# EX_IO.net
KiCad netlist of a schematic drawn in Altium Designer
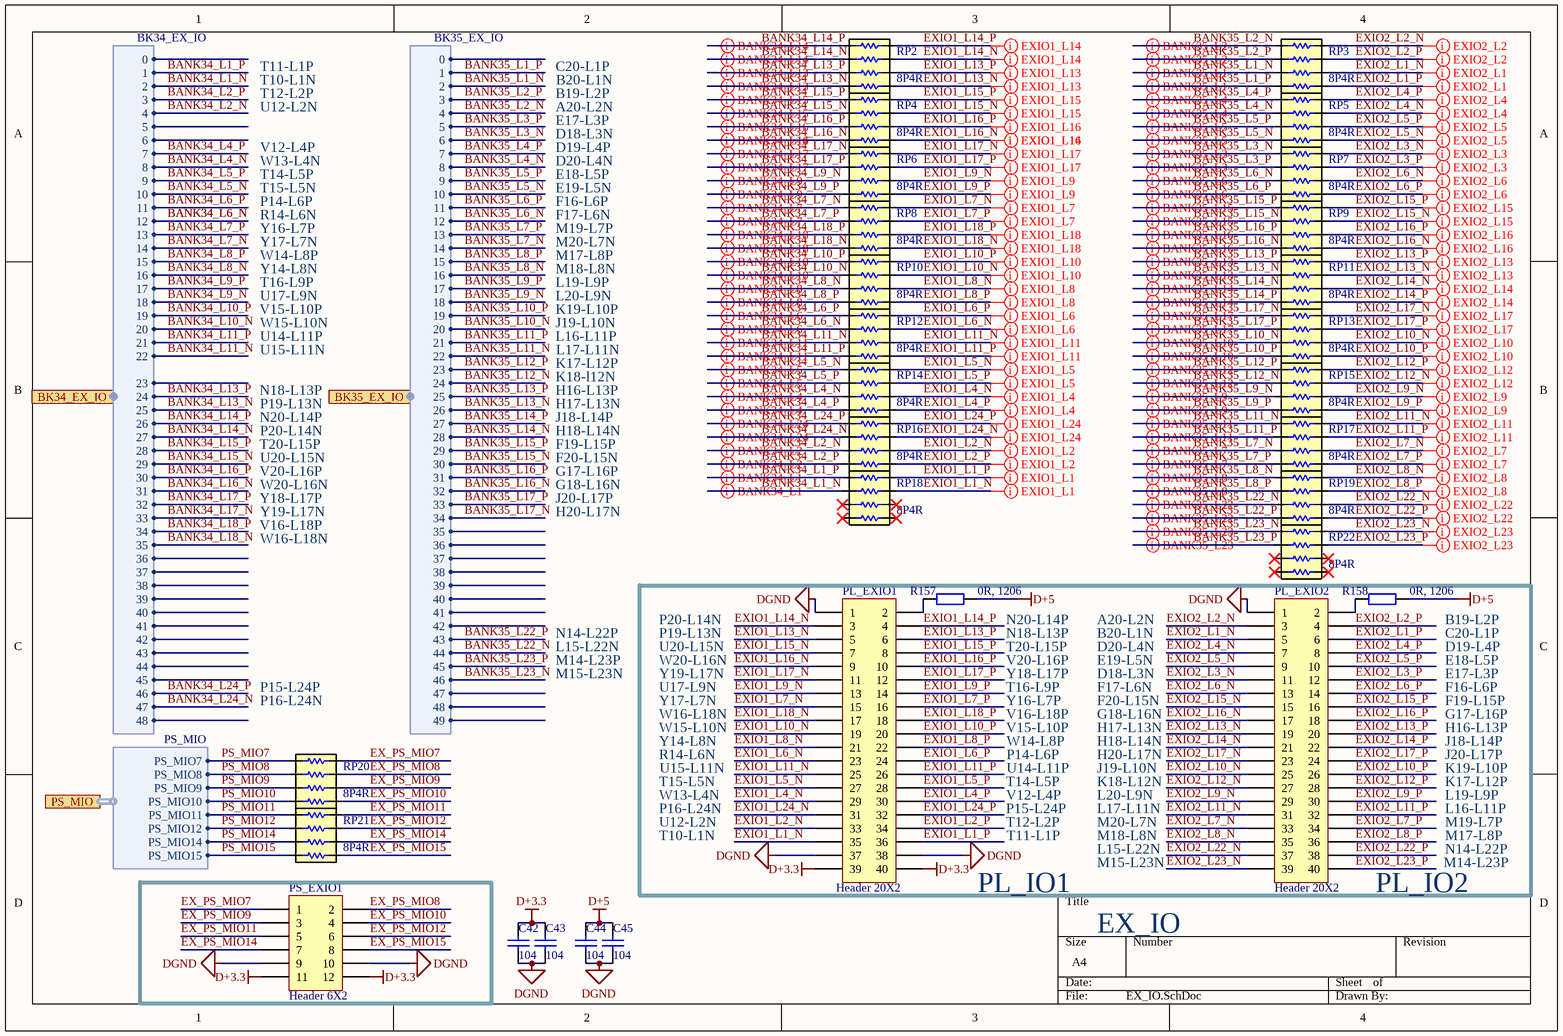
[diagram p0: EX_IO.SchDoc]

(export (version "E")
  (design (tool "Eeschema 10.0.6"))
  (components
    (comp (ref "C42")
      (value "104")
      (footprint "C 0402_LL")
      (description "Capacitor")
      (fields (field (name "PUBLISHER") "Altium Limited"))
      (libsource (lib "Miscellaneous Devices") (part "Cap"))
    )
    (comp (ref "C43")
      (value "104")
      (footprint "C 0402_LL")
      (description "Capacitor")
      (fields (field (name "PUBLISHER") "Altium Limited"))
      (libsource (lib "Miscellaneous Devices") (part "Cap"))
    )
    (comp (ref "C44")
      (value "104")
      (footprint "C 0402_LL")
      (description "Capacitor")
      (fields (field (name "PUBLISHER") "Altium Limited"))
      (libsource (lib "Miscellaneous Devices") (part "Cap"))
    )
    (comp (ref "C45")
      (value "104")
      (footprint "C 0402_LL")
      (description "Capacitor")
      (fields (field (name "PUBLISHER") "Altium Limited"))
      (libsource (lib "Miscellaneous Devices") (part "Cap"))
    )
    (comp (ref "PL_EXIO1")
      (value "Header 20X2")
      (footprint "HDR2.54-LI-2x20P")
      (description "Header, 20-Pin, Dual row")
      (fields (field (name "PUBLISHER") "Altium Limited"))
      (libsource (lib "Miscellaneous Connectors") (part "Header 20X2"))
    )
    (comp (ref "PL_EXIO2")
      (value "Header 20X2")
      (footprint "HDR2.54-LI-2x20P")
      (description "Header, 20-Pin, Dual row")
      (fields (field (name "PUBLISHER") "Altium Limited"))
      (libsource (lib "ZYNQ7010_add") (part "Header 20X2"))
    )
    (comp (ref "PS_EXIO1")
      (value "Header 6X2")
      (footprint "HDR2X6")
      (description "Header, 6-Pin, Dual row")
      (fields (field (name "PUBLISHER") "Altium Limited"))
      (libsource (lib "Miscellaneous Connectors") (part "Header 6X2"))
    )
    (comp (ref "R157")
      (value "0R, 1206")
      (footprint "R 1206_L")
      (description "Resistor")
      (fields (field (name "PUBLISHER") "Altium Limited"))
      (libsource (lib "Miscellaneous Devices") (part "Res2"))
    )
    (comp (ref "R158")
      (value "0R, 1206")
      (footprint "R 1206_L")
      (description "Resistor")
      (fields (field (name "PUBLISHER") "Altium Limited"))
      (libsource (lib "Miscellaneous Devices") (part "Res2"))
    )
    (comp (ref "RP2")
      (value "8P4R")
      (footprint "8P4R")
      (description "贴片排阻")
      (fields (field (name "MANUFACTURER") "NC"))
      (libsource (lib "ZYNQ7010_add") (part "8P4R"))
    )
    (comp (ref "RP3")
      (value "8P4R")
      (footprint "8P4R")
      (description "贴片排阻")
      (fields (field (name "MANUFACTURER") "NC"))
      (libsource (lib "ZYNQ7010_add") (part "8P4R"))
    )
    (comp (ref "RP4")
      (value "8P4R")
      (footprint "8P4R")
      (description "贴片排阻")
      (fields (field (name "MANUFACTURER") "NC"))
      (libsource (lib "ZYNQ7010_add") (part "8P4R"))
    )
    (comp (ref "RP5")
      (value "8P4R")
      (footprint "8P4R")
      (description "贴片排阻")
      (fields (field (name "MANUFACTURER") "NC"))
      (libsource (lib "ZYNQ7010_add") (part "8P4R"))
    )
    (comp (ref "RP6")
      (value "8P4R")
      (footprint "8P4R")
      (description "贴片排阻")
      (fields (field (name "MANUFACTURER") "NC"))
      (libsource (lib "ZYNQ7010_add") (part "8P4R"))
    )
    (comp (ref "RP7")
      (value "8P4R")
      (footprint "8P4R")
      (description "贴片排阻")
      (fields (field (name "MANUFACTURER") "NC"))
      (libsource (lib "ZYNQ7010_add") (part "8P4R"))
    )
    (comp (ref "RP8")
      (value "8P4R")
      (footprint "8P4R")
      (description "贴片排阻")
      (fields (field (name "MANUFACTURER") "NC"))
      (libsource (lib "ZYNQ7010_add") (part "8P4R"))
    )
    (comp (ref "RP9")
      (value "8P4R")
      (footprint "8P4R")
      (description "贴片排阻")
      (fields (field (name "MANUFACTURER") "NC"))
      (libsource (lib "ZYNQ7010_add") (part "8P4R"))
    )
    (comp (ref "RP10")
      (value "8P4R")
      (footprint "8P4R")
      (description "贴片排阻")
      (fields (field (name "MANUFACTURER") "NC"))
      (libsource (lib "ZYNQ7010_add") (part "8P4R"))
    )
    (comp (ref "RP11")
      (value "8P4R")
      (footprint "8P4R")
      (description "贴片排阻")
      (fields (field (name "MANUFACTURER") "NC"))
      (libsource (lib "ZYNQ7010_add") (part "8P4R"))
    )
    (comp (ref "RP12")
      (value "8P4R")
      (footprint "8P4R")
      (description "贴片排阻")
      (fields (field (name "MANUFACTURER") "NC"))
      (libsource (lib "ZYNQ7010_add") (part "8P4R"))
    )
    (comp (ref "RP13")
      (value "8P4R")
      (footprint "8P4R")
      (description "贴片排阻")
      (fields (field (name "MANUFACTURER") "NC"))
      (libsource (lib "ZYNQ7010_add") (part "8P4R"))
    )
    (comp (ref "RP14")
      (value "8P4R")
      (footprint "8P4R")
      (description "贴片排阻")
      (fields (field (name "MANUFACTURER") "NC"))
      (libsource (lib "ZYNQ7010_add") (part "8P4R"))
    )
    (comp (ref "RP15")
      (value "8P4R")
      (footprint "8P4R")
      (description "贴片排阻")
      (fields (field (name "MANUFACTURER") "NC"))
      (libsource (lib "ZYNQ7010_add") (part "8P4R"))
    )
    (comp (ref "RP16")
      (value "8P4R")
      (footprint "8P4R")
      (description "贴片排阻")
      (fields (field (name "MANUFACTURER") "NC"))
      (libsource (lib "ZYNQ7010_add") (part "8P4R"))
    )
    (comp (ref "RP17")
      (value "8P4R")
      (footprint "8P4R")
      (description "贴片排阻")
      (fields (field (name "MANUFACTURER") "NC"))
      (libsource (lib "ZYNQ7010_add") (part "8P4R"))
    )
    (comp (ref "RP18")
      (value "8P4R")
      (footprint "8P4R")
      (description "贴片排阻")
      (fields (field (name "MANUFACTURER") "NC"))
      (libsource (lib "ZYNQ7010_add") (part "8P4R"))
    )
    (comp (ref "RP19")
      (value "8P4R")
      (footprint "8P4R")
      (description "贴片排阻")
      (fields (field (name "MANUFACTURER") "NC"))
      (libsource (lib "ZYNQ7010_add") (part "8P4R"))
    )
    (comp (ref "RP20")
      (value "8P4R")
      (footprint "8P4R")
      (description "贴片排阻")
      (fields (field (name "MANUFACTURER") "NC"))
      (libsource (lib "ZYNQ7010_add") (part "8P4R"))
    )
    (comp (ref "RP21")
      (value "8P4R")
      (footprint "8P4R")
      (description "贴片排阻")
      (fields (field (name "MANUFACTURER") "NC"))
      (libsource (lib "ZYNQ7010_add") (part "8P4R"))
    )
    (comp (ref "RP22")
      (value "8P4R")
      (footprint "8P4R")
      (description "贴片排阻")
      (fields (field (name "MANUFACTURER") "NC"))
      (libsource (lib "ZYNQ7010_add") (part "8P4R"))
    )
  )
  (nets
    (net (code "4") (name "/BANK34_L1_N") (class "Default")
      (node (ref "RP18") (pin "2") (pinfunction "2_2") (pintype "passive"))
    )
    (net (code "5") (name "/BANK34_L1_P") (class "Default")
      (node (ref "RP18") (pin "1") (pinfunction "1_1") (pintype "passive"))
    )
    (net (code "6") (name "/BANK34_L2_N") (class "Default")
      (node (ref "RP16") (pin "3") (pinfunction "3_3") (pintype "passive"))
    )
    (net (code "7") (name "/BANK34_L2_P") (class "Default")
      (node (ref "RP16") (pin "4") (pinfunction "4_4") (pintype "passive"))
    )
    (net (code "8") (name "/BANK34_L4_N") (class "Default")
      (node (ref "RP14") (pin "3") (pinfunction "3_3") (pintype "passive"))
    )
    (net (code "9") (name "/BANK34_L4_P") (class "Default")
      (node (ref "RP14") (pin "4") (pinfunction "4_4") (pintype "passive"))
    )
    (net (code "10") (name "/BANK34_L5_N") (class "Default")
      (node (ref "RP14") (pin "1") (pinfunction "1_1") (pintype "passive"))
    )
    (net (code "11") (name "/BANK34_L5_P") (class "Default")
      (node (ref "RP14") (pin "2") (pinfunction "2_2") (pintype "passive"))
    )
    (net (code "12") (name "/BANK34_L6_N") (class "Default")
      (node (ref "RP12") (pin "2") (pinfunction "2_2") (pintype "passive"))
    )
    (net (code "13") (name "/BANK34_L6_P") (class "Default")
      (node (ref "RP12") (pin "1") (pinfunction "1_1") (pintype "passive"))
    )
    (net (code "14") (name "/BANK34_L7_N") (class "Default")
      (node (ref "RP8") (pin "1") (pinfunction "1_1") (pintype "passive"))
    )
    (net (code "15") (name "/BANK34_L7_P") (class "Default")
      (node (ref "RP8") (pin "2") (pinfunction "2_2") (pintype "passive"))
    )
    (net (code "16") (name "/BANK34_L8_N") (class "Default")
      (node (ref "RP10") (pin "3") (pinfunction "3_3") (pintype "passive"))
    )
    (net (code "17") (name "/BANK34_L8_P") (class "Default")
      (node (ref "RP10") (pin "4") (pinfunction "4_4") (pintype "passive"))
    )
    (net (code "18") (name "/BANK34_L9_N") (class "Default")
      (node (ref "RP6") (pin "3") (pinfunction "3_3") (pintype "passive"))
    )
    (net (code "19") (name "/BANK34_L9_P") (class "Default")
      (node (ref "RP6") (pin "4") (pinfunction "4_4") (pintype "passive"))
    )
    (net (code "20") (name "/BANK34_L10_N") (class "Default")
      (node (ref "RP10") (pin "2") (pinfunction "2_2") (pintype "passive"))
    )
    (net (code "21") (name "/BANK34_L10_P") (class "Default")
      (node (ref "RP10") (pin "1") (pinfunction "1_1") (pintype "passive"))
    )
    (net (code "22") (name "/BANK34_L11_N") (class "Default")
      (node (ref "RP12") (pin "3") (pinfunction "3_3") (pintype "passive"))
    )
    (net (code "23") (name "/BANK34_L11_P") (class "Default")
      (node (ref "RP12") (pin "4") (pinfunction "4_4") (pintype "passive"))
    )
    (net (code "24") (name "/BANK34_L13_N") (class "Default")
      (node (ref "RP2") (pin "4") (pinfunction "4_4") (pintype "passive"))
    )
    (net (code "25") (name "/BANK34_L13_P") (class "Default")
      (node (ref "RP2") (pin "3") (pinfunction "3_3") (pintype "passive"))
    )
    (net (code "26") (name "/BANK34_L14_N") (class "Default")
      (node (ref "RP2") (pin "2") (pinfunction "2_2") (pintype "passive"))
    )
    (net (code "27") (name "/BANK34_L14_P") (class "Default")
      (node (ref "RP2") (pin "1") (pinfunction "1_1") (pintype "passive"))
    )
    (net (code "28") (name "/BANK34_L15_N") (class "Default")
      (node (ref "RP4") (pin "2") (pinfunction "2_2") (pintype "passive"))
    )
    (net (code "29") (name "/BANK34_L15_P") (class "Default")
      (node (ref "RP4") (pin "1") (pinfunction "1_1") (pintype "passive"))
    )
    (net (code "30") (name "/BANK34_L16_N") (class "Default")
      (node (ref "RP4") (pin "4") (pinfunction "4_4") (pintype "passive"))
    )
    (net (code "31") (name "/BANK34_L16_P") (class "Default")
      (node (ref "RP4") (pin "3") (pinfunction "3_3") (pintype "passive"))
    )
    (net (code "32") (name "/BANK34_L17_N") (class "Default")
      (node (ref "RP6") (pin "1") (pinfunction "1_1") (pintype "passive"))
    )
    (net (code "33") (name "/BANK34_L17_P") (class "Default")
      (node (ref "RP6") (pin "2") (pinfunction "2_2") (pintype "passive"))
    )
    (net (code "34") (name "/BANK34_L18_N") (class "Default")
      (node (ref "RP8") (pin "4") (pinfunction "4_4") (pintype "passive"))
    )
    (net (code "35") (name "/BANK34_L18_P") (class "Default")
      (node (ref "RP8") (pin "3") (pinfunction "3_3") (pintype "passive"))
    )
    (net (code "36") (name "/BANK34_L24_N") (class "Default")
      (node (ref "RP16") (pin "2") (pinfunction "2_2") (pintype "passive"))
    )
    (net (code "37") (name "/BANK34_L24_P") (class "Default")
      (node (ref "RP16") (pin "1") (pinfunction "1_1") (pintype "passive"))
    )
    (net (code "38") (name "/BANK35_L1_N") (class "Default")
      (node (ref "RP3") (pin "3") (pinfunction "3_3") (pintype "passive"))
    )
    (net (code "39") (name "/BANK35_L1_P") (class "Default")
      (node (ref "RP3") (pin "4") (pinfunction "4_4") (pintype "passive"))
    )
    (net (code "40") (name "/BANK35_L2_N") (class "Default")
      (node (ref "RP3") (pin "1") (pinfunction "1_1") (pintype "passive"))
    )
    (net (code "41") (name "/BANK35_L2_P") (class "Default")
      (node (ref "RP3") (pin "2") (pinfunction "2_2") (pintype "passive"))
    )
    (net (code "42") (name "/BANK35_L3_N") (class "Default")
      (node (ref "RP7") (pin "1") (pinfunction "1_1") (pintype "passive"))
    )
    (net (code "43") (name "/BANK35_L3_P") (class "Default")
      (node (ref "RP7") (pin "2") (pinfunction "2_2") (pintype "passive"))
    )
    (net (code "44") (name "/BANK35_L4_N") (class "Default")
      (node (ref "RP5") (pin "2") (pinfunction "2_2") (pintype "passive"))
    )
    (net (code "45") (name "/BANK35_L4_P") (class "Default")
      (node (ref "RP5") (pin "1") (pinfunction "1_1") (pintype "passive"))
    )
    (net (code "46") (name "/BANK35_L5_N") (class "Default")
      (node (ref "RP5") (pin "4") (pinfunction "4_4") (pintype "passive"))
    )
    (net (code "47") (name "/BANK35_L5_P") (class "Default")
      (node (ref "RP5") (pin "3") (pinfunction "3_3") (pintype "passive"))
    )
    (net (code "48") (name "/BANK35_L6_N") (class "Default")
      (node (ref "RP7") (pin "3") (pinfunction "3_3") (pintype "passive"))
    )
    (net (code "49") (name "/BANK35_L6_P") (class "Default")
      (node (ref "RP7") (pin "4") (pinfunction "4_4") (pintype "passive"))
    )
    (net (code "50") (name "/BANK35_L7_N") (class "Default")
      (node (ref "RP17") (pin "3") (pinfunction "3_3") (pintype "passive"))
    )
    (net (code "51") (name "/BANK35_L7_P") (class "Default")
      (node (ref "RP17") (pin "4") (pinfunction "4_4") (pintype "passive"))
    )
    (net (code "52") (name "/BANK35_L8_N") (class "Default")
      (node (ref "RP19") (pin "1") (pinfunction "1_1") (pintype "passive"))
    )
    (net (code "53") (name "/BANK35_L8_P") (class "Default")
      (node (ref "RP19") (pin "2") (pinfunction "2_2") (pintype "passive"))
    )
    (net (code "54") (name "/BANK35_L9_N") (class "Default")
      (node (ref "RP15") (pin "3") (pinfunction "3_3") (pintype "passive"))
    )
    (net (code "55") (name "/BANK35_L9_P") (class "Default")
      (node (ref "RP15") (pin "4") (pinfunction "4_4") (pintype "passive"))
    )
    (net (code "56") (name "/BANK35_L10_N") (class "Default")
      (node (ref "RP13") (pin "3") (pinfunction "3_3") (pintype "passive"))
    )
    (net (code "57") (name "/BANK35_L10_P") (class "Default")
      (node (ref "RP13") (pin "4") (pinfunction "4_4") (pintype "passive"))
    )
    (net (code "58") (name "/BANK35_L11_N") (class "Default")
      (node (ref "RP17") (pin "1") (pinfunction "1_1") (pintype "passive"))
    )
    (net (code "59") (name "/BANK35_L11_P") (class "Default")
      (node (ref "RP17") (pin "2") (pinfunction "2_2") (pintype "passive"))
    )
    (net (code "60") (name "/BANK35_L12_N") (class "Default")
      (node (ref "RP15") (pin "2") (pinfunction "2_2") (pintype "passive"))
    )
    (net (code "61") (name "/BANK35_L12_P") (class "Default")
      (node (ref "RP15") (pin "1") (pinfunction "1_1") (pintype "passive"))
    )
    (net (code "62") (name "/BANK35_L13_N") (class "Default")
      (node (ref "RP11") (pin "2") (pinfunction "2_2") (pintype "passive"))
    )
    (net (code "63") (name "/BANK35_L13_P") (class "Default")
      (node (ref "RP11") (pin "1") (pinfunction "1_1") (pintype "passive"))
    )
    (net (code "64") (name "/BANK35_L14_N") (class "Default")
      (node (ref "RP11") (pin "3") (pinfunction "3_3") (pintype "passive"))
    )
    (net (code "65") (name "/BANK35_L14_P") (class "Default")
      (node (ref "RP11") (pin "4") (pinfunction "4_4") (pintype "passive"))
    )
    (net (code "66") (name "/BANK35_L15_N") (class "Default")
      (node (ref "RP9") (pin "2") (pinfunction "2_2") (pintype "passive"))
    )
    (net (code "67") (name "/BANK35_L15_P") (class "Default")
      (node (ref "RP9") (pin "1") (pinfunction "1_1") (pintype "passive"))
    )
    (net (code "68") (name "/BANK35_L16_N") (class "Default")
      (node (ref "RP9") (pin "4") (pinfunction "4_4") (pintype "passive"))
    )
    (net (code "69") (name "/BANK35_L16_P") (class "Default")
      (node (ref "RP9") (pin "3") (pinfunction "3_3") (pintype "passive"))
    )
    (net (code "70") (name "/BANK35_L17_N") (class "Default")
      (node (ref "RP13") (pin "1") (pinfunction "1_1") (pintype "passive"))
    )
    (net (code "71") (name "/BANK35_L17_P") (class "Default")
      (node (ref "RP13") (pin "2") (pinfunction "2_2") (pintype "passive"))
    )
    (net (code "72") (name "/BANK35_L22_N") (class "Default")
      (node (ref "RP19") (pin "3") (pinfunction "3_3") (pintype "passive"))
    )
    (net (code "73") (name "/BANK35_L22_P") (class "Default")
      (node (ref "RP19") (pin "4") (pinfunction "4_4") (pintype "passive"))
    )
    (net (code "74") (name "/BANK35_L23_N") (class "Default")
      (node (ref "RP22") (pin "1") (pinfunction "1_1") (pintype "passive"))
    )
    (net (code "75") (name "/BANK35_L23_P") (class "Default")
      (node (ref "RP22") (pin "2") (pinfunction "2_2") (pintype "passive"))
    )
    (net (code "76") (name "/EXIO1_L1_N") (class "Default")
      (node (ref "PL_EXIO1") (pin "35") (pinfunction "35_35") (pintype "passive"))
      (node (ref "RP18") (pin "6") (pinfunction "6_6") (pintype "passive"))
    )
    (net (code "77") (name "/EXIO1_L1_P") (class "Default")
      (node (ref "PL_EXIO1") (pin "36") (pinfunction "36_36") (pintype "passive"))
      (node (ref "RP18") (pin "5") (pinfunction "5_5") (pintype "passive"))
    )
    (net (code "78") (name "/EXIO1_L2_N") (class "Default")
      (node (ref "PL_EXIO1") (pin "33") (pinfunction "33_33") (pintype "passive"))
      (node (ref "RP16") (pin "7") (pinfunction "7_7") (pintype "passive"))
    )
    (net (code "79") (name "/EXIO1_L2_P") (class "Default")
      (node (ref "PL_EXIO1") (pin "34") (pinfunction "34_34") (pintype "passive"))
      (node (ref "RP16") (pin "8") (pinfunction "8_8") (pintype "passive"))
    )
    (net (code "80") (name "/EXIO1_L4_N") (class "Default")
      (node (ref "PL_EXIO1") (pin "29") (pinfunction "29_29") (pintype "passive"))
      (node (ref "RP14") (pin "7") (pinfunction "7_7") (pintype "passive"))
    )
    (net (code "81") (name "/EXIO1_L4_P") (class "Default")
      (node (ref "PL_EXIO1") (pin "30") (pinfunction "30_30") (pintype "passive"))
      (node (ref "RP14") (pin "8") (pinfunction "8_8") (pintype "passive"))
    )
    (net (code "82") (name "/EXIO1_L5_N") (class "Default")
      (node (ref "PL_EXIO1") (pin "27") (pinfunction "27_27") (pintype "passive"))
      (node (ref "RP14") (pin "5") (pinfunction "5_5") (pintype "passive"))
    )
    (net (code "83") (name "/EXIO1_L5_P") (class "Default")
      (node (ref "PL_EXIO1") (pin "28") (pinfunction "28_28") (pintype "passive"))
      (node (ref "RP14") (pin "6") (pinfunction "6_6") (pintype "passive"))
    )
    (net (code "84") (name "/EXIO1_L6_N") (class "Default")
      (node (ref "PL_EXIO1") (pin "23") (pinfunction "23_23") (pintype "passive"))
      (node (ref "RP12") (pin "6") (pinfunction "6_6") (pintype "passive"))
    )
    (net (code "85") (name "/EXIO1_L6_P") (class "Default")
      (node (ref "PL_EXIO1") (pin "24") (pinfunction "24_24") (pintype "passive"))
      (node (ref "RP12") (pin "5") (pinfunction "5_5") (pintype "passive"))
    )
    (net (code "86") (name "/EXIO1_L7_N") (class "Default")
      (node (ref "PL_EXIO1") (pin "15") (pinfunction "15_15") (pintype "passive"))
      (node (ref "RP8") (pin "5") (pinfunction "5_5") (pintype "passive"))
    )
    (net (code "87") (name "/EXIO1_L7_P") (class "Default")
      (node (ref "PL_EXIO1") (pin "16") (pinfunction "16_16") (pintype "passive"))
      (node (ref "RP8") (pin "6") (pinfunction "6_6") (pintype "passive"))
    )
    (net (code "88") (name "/EXIO1_L8_N") (class "Default")
      (node (ref "PL_EXIO1") (pin "21") (pinfunction "21_21") (pintype "passive"))
      (node (ref "RP10") (pin "7") (pinfunction "7_7") (pintype "passive"))
    )
    (net (code "89") (name "/EXIO1_L8_P") (class "Default")
      (node (ref "PL_EXIO1") (pin "22") (pinfunction "22_22") (pintype "passive"))
      (node (ref "RP10") (pin "8") (pinfunction "8_8") (pintype "passive"))
    )
    (net (code "90") (name "/EXIO1_L9_N") (class "Default")
      (node (ref "PL_EXIO1") (pin "13") (pinfunction "13_13") (pintype "passive"))
      (node (ref "RP6") (pin "7") (pinfunction "7_7") (pintype "passive"))
    )
    (net (code "91") (name "/EXIO1_L9_P") (class "Default")
      (node (ref "PL_EXIO1") (pin "14") (pinfunction "14_14") (pintype "passive"))
      (node (ref "RP6") (pin "8") (pinfunction "8_8") (pintype "passive"))
    )
    (net (code "92") (name "/EXIO1_L10_N") (class "Default")
      (node (ref "PL_EXIO1") (pin "19") (pinfunction "19_19") (pintype "passive"))
      (node (ref "RP10") (pin "6") (pinfunction "6_6") (pintype "passive"))
    )
    (net (code "93") (name "/EXIO1_L10_P") (class "Default")
      (node (ref "PL_EXIO1") (pin "20") (pinfunction "20_20") (pintype "passive"))
      (node (ref "RP10") (pin "5") (pinfunction "5_5") (pintype "passive"))
    )
    (net (code "94") (name "/EXIO1_L11_N") (class "Default")
      (node (ref "PL_EXIO1") (pin "25") (pinfunction "25_25") (pintype "passive"))
      (node (ref "RP12") (pin "7") (pinfunction "7_7") (pintype "passive"))
    )
    (net (code "95") (name "/EXIO1_L11_P") (class "Default")
      (node (ref "PL_EXIO1") (pin "26") (pinfunction "26_26") (pintype "passive"))
      (node (ref "RP12") (pin "8") (pinfunction "8_8") (pintype "passive"))
    )
    (net (code "96") (name "/EXIO1_L13_N") (class "Default")
      (node (ref "PL_EXIO1") (pin "5") (pinfunction "5_5") (pintype "passive"))
      (node (ref "RP2") (pin "8") (pinfunction "8_8") (pintype "passive"))
    )
    (net (code "97") (name "/EXIO1_L13_P") (class "Default")
      (node (ref "PL_EXIO1") (pin "6") (pinfunction "6_6") (pintype "passive"))
      (node (ref "RP2") (pin "7") (pinfunction "7_7") (pintype "passive"))
    )
    (net (code "98") (name "/EXIO1_L14_N") (class "Default")
      (node (ref "PL_EXIO1") (pin "3") (pinfunction "3_3") (pintype "passive"))
      (node (ref "RP2") (pin "6") (pinfunction "6_6") (pintype "passive"))
    )
    (net (code "99") (name "/EXIO1_L14_P") (class "Default")
      (node (ref "PL_EXIO1") (pin "4") (pinfunction "4_4") (pintype "passive"))
      (node (ref "RP2") (pin "5") (pinfunction "5_5") (pintype "passive"))
    )
    (net (code "100") (name "/EXIO1_L15_N") (class "Default")
      (node (ref "PL_EXIO1") (pin "7") (pinfunction "7_7") (pintype "passive"))
      (node (ref "RP4") (pin "6") (pinfunction "6_6") (pintype "passive"))
    )
    (net (code "101") (name "/EXIO1_L15_P") (class "Default")
      (node (ref "PL_EXIO1") (pin "8") (pinfunction "8_8") (pintype "passive"))
      (node (ref "RP4") (pin "5") (pinfunction "5_5") (pintype "passive"))
    )
    (net (code "102") (name "/EXIO1_L16_N") (class "Default")
      (node (ref "PL_EXIO1") (pin "9") (pinfunction "9_9") (pintype "passive"))
      (node (ref "RP4") (pin "8") (pinfunction "8_8") (pintype "passive"))
    )
    (net (code "103") (name "/EXIO1_L16_P") (class "Default")
      (node (ref "PL_EXIO1") (pin "10") (pinfunction "10_10") (pintype "passive"))
      (node (ref "RP4") (pin "7") (pinfunction "7_7") (pintype "passive"))
    )
    (net (code "104") (name "/EXIO1_L17_N") (class "Default")
      (node (ref "PL_EXIO1") (pin "11") (pinfunction "11_11") (pintype "passive"))
      (node (ref "RP6") (pin "5") (pinfunction "5_5") (pintype "passive"))
    )
    (net (code "105") (name "/EXIO1_L17_P") (class "Default")
      (node (ref "PL_EXIO1") (pin "12") (pinfunction "12_12") (pintype "passive"))
      (node (ref "RP6") (pin "6") (pinfunction "6_6") (pintype "passive"))
    )
    (net (code "106") (name "/EXIO1_L18_N") (class "Default")
      (node (ref "PL_EXIO1") (pin "17") (pinfunction "17_17") (pintype "passive"))
      (node (ref "RP8") (pin "8") (pinfunction "8_8") (pintype "passive"))
    )
    (net (code "107") (name "/EXIO1_L18_P") (class "Default")
      (node (ref "PL_EXIO1") (pin "18") (pinfunction "18_18") (pintype "passive"))
      (node (ref "RP8") (pin "7") (pinfunction "7_7") (pintype "passive"))
    )
    (net (code "108") (name "/EXIO1_L24_N") (class "Default")
      (node (ref "PL_EXIO1") (pin "31") (pinfunction "31_31") (pintype "passive"))
      (node (ref "RP16") (pin "6") (pinfunction "6_6") (pintype "passive"))
    )
    (net (code "109") (name "/EXIO1_L24_P") (class "Default")
      (node (ref "PL_EXIO1") (pin "32") (pinfunction "32_32") (pintype "passive"))
      (node (ref "RP16") (pin "5") (pinfunction "5_5") (pintype "passive"))
    )
    (net (code "110") (name "/EXIO2_L1_N") (class "Default")
      (node (ref "PL_EXIO2") (pin "5") (pinfunction "5_5") (pintype "passive"))
      (node (ref "RP3") (pin "7") (pinfunction "7_7") (pintype "passive"))
    )
    (net (code "111") (name "/EXIO2_L1_P") (class "Default")
      (node (ref "PL_EXIO2") (pin "6") (pinfunction "6_6") (pintype "passive"))
      (node (ref "RP3") (pin "8") (pinfunction "8_8") (pintype "passive"))
    )
    (net (code "112") (name "/EXIO2_L2_N") (class "Default")
      (node (ref "PL_EXIO2") (pin "3") (pinfunction "3_3") (pintype "passive"))
      (node (ref "RP3") (pin "5") (pinfunction "5_5") (pintype "passive"))
    )
    (net (code "113") (name "/EXIO2_L2_P") (class "Default")
      (node (ref "PL_EXIO2") (pin "4") (pinfunction "4_4") (pintype "passive"))
      (node (ref "RP3") (pin "6") (pinfunction "6_6") (pintype "passive"))
    )
    (net (code "114") (name "/EXIO2_L3_N") (class "Default")
      (node (ref "PL_EXIO2") (pin "11") (pinfunction "11_11") (pintype "passive"))
      (node (ref "RP7") (pin "5") (pinfunction "5_5") (pintype "passive"))
    )
    (net (code "115") (name "/EXIO2_L3_P") (class "Default")
      (node (ref "PL_EXIO2") (pin "12") (pinfunction "12_12") (pintype "passive"))
      (node (ref "RP7") (pin "6") (pinfunction "6_6") (pintype "passive"))
    )
    (net (code "116") (name "/EXIO2_L4_N") (class "Default")
      (node (ref "PL_EXIO2") (pin "7") (pinfunction "7_7") (pintype "passive"))
      (node (ref "RP5") (pin "6") (pinfunction "6_6") (pintype "passive"))
    )
    (net (code "117") (name "/EXIO2_L4_P") (class "Default")
      (node (ref "PL_EXIO2") (pin "8") (pinfunction "8_8") (pintype "passive"))
      (node (ref "RP5") (pin "5") (pinfunction "5_5") (pintype "passive"))
    )
    (net (code "118") (name "/EXIO2_L5_N") (class "Default")
      (node (ref "PL_EXIO2") (pin "9") (pinfunction "9_9") (pintype "passive"))
      (node (ref "RP5") (pin "8") (pinfunction "8_8") (pintype "passive"))
    )
    (net (code "119") (name "/EXIO2_L5_P") (class "Default")
      (node (ref "PL_EXIO2") (pin "10") (pinfunction "10_10") (pintype "passive"))
      (node (ref "RP5") (pin "7") (pinfunction "7_7") (pintype "passive"))
    )
    (net (code "120") (name "/EXIO2_L6_N") (class "Default")
      (node (ref "PL_EXIO2") (pin "13") (pinfunction "13_13") (pintype "passive"))
      (node (ref "RP7") (pin "7") (pinfunction "7_7") (pintype "passive"))
    )
    (net (code "121") (name "/EXIO2_L6_P") (class "Default")
      (node (ref "PL_EXIO2") (pin "14") (pinfunction "14_14") (pintype "passive"))
      (node (ref "RP7") (pin "8") (pinfunction "8_8") (pintype "passive"))
    )
    (net (code "122") (name "/EXIO2_L7_N") (class "Default")
      (node (ref "PL_EXIO2") (pin "33") (pinfunction "33_33") (pintype "passive"))
      (node (ref "RP17") (pin "7") (pinfunction "7_7") (pintype "passive"))
    )
    (net (code "123") (name "/EXIO2_L7_P") (class "Default")
      (node (ref "PL_EXIO2") (pin "34") (pinfunction "34_34") (pintype "passive"))
      (node (ref "RP17") (pin "8") (pinfunction "8_8") (pintype "passive"))
    )
    (net (code "124") (name "/EXIO2_L8_N") (class "Default")
      (node (ref "PL_EXIO2") (pin "35") (pinfunction "35_35") (pintype "passive"))
      (node (ref "RP19") (pin "5") (pinfunction "5_5") (pintype "passive"))
    )
    (net (code "125") (name "/EXIO2_L8_P") (class "Default")
      (node (ref "PL_EXIO2") (pin "36") (pinfunction "36_36") (pintype "passive"))
      (node (ref "RP19") (pin "6") (pinfunction "6_6") (pintype "passive"))
    )
    (net (code "126") (name "/EXIO2_L9_N") (class "Default")
      (node (ref "PL_EXIO2") (pin "29") (pinfunction "29_29") (pintype "passive"))
      (node (ref "RP15") (pin "7") (pinfunction "7_7") (pintype "passive"))
    )
    (net (code "127") (name "/EXIO2_L9_P") (class "Default")
      (node (ref "PL_EXIO2") (pin "30") (pinfunction "30_30") (pintype "passive"))
      (node (ref "RP15") (pin "8") (pinfunction "8_8") (pintype "passive"))
    )
    (net (code "128") (name "/EXIO2_L10_N") (class "Default")
      (node (ref "PL_EXIO2") (pin "25") (pinfunction "25_25") (pintype "passive"))
      (node (ref "RP13") (pin "7") (pinfunction "7_7") (pintype "passive"))
    )
    (net (code "129") (name "/EXIO2_L10_P") (class "Default")
      (node (ref "PL_EXIO2") (pin "26") (pinfunction "26_26") (pintype "passive"))
      (node (ref "RP13") (pin "8") (pinfunction "8_8") (pintype "passive"))
    )
    (net (code "130") (name "/EXIO2_L11_N") (class "Default")
      (node (ref "PL_EXIO2") (pin "31") (pinfunction "31_31") (pintype "passive"))
      (node (ref "RP17") (pin "5") (pinfunction "5_5") (pintype "passive"))
    )
    (net (code "131") (name "/EXIO2_L11_P") (class "Default")
      (node (ref "PL_EXIO2") (pin "32") (pinfunction "32_32") (pintype "passive"))
      (node (ref "RP17") (pin "6") (pinfunction "6_6") (pintype "passive"))
    )
    (net (code "132") (name "/EXIO2_L12_N") (class "Default")
      (node (ref "PL_EXIO2") (pin "27") (pinfunction "27_27") (pintype "passive"))
      (node (ref "RP15") (pin "6") (pinfunction "6_6") (pintype "passive"))
    )
    (net (code "133") (name "/EXIO2_L12_P") (class "Default")
      (node (ref "PL_EXIO2") (pin "28") (pinfunction "28_28") (pintype "passive"))
      (node (ref "RP15") (pin "5") (pinfunction "5_5") (pintype "passive"))
    )
    (net (code "134") (name "/EXIO2_L13_N") (class "Default")
      (node (ref "PL_EXIO2") (pin "19") (pinfunction "19_19") (pintype "passive"))
      (node (ref "RP11") (pin "6") (pinfunction "6_6") (pintype "passive"))
    )
    (net (code "135") (name "/EXIO2_L13_P") (class "Default")
      (node (ref "PL_EXIO2") (pin "20") (pinfunction "20_20") (pintype "passive"))
      (node (ref "RP11") (pin "5") (pinfunction "5_5") (pintype "passive"))
    )
    (net (code "136") (name "/EXIO2_L14_N") (class "Default")
      (node (ref "PL_EXIO2") (pin "21") (pinfunction "21_21") (pintype "passive"))
      (node (ref "RP11") (pin "7") (pinfunction "7_7") (pintype "passive"))
    )
    (net (code "137") (name "/EXIO2_L14_P") (class "Default")
      (node (ref "PL_EXIO2") (pin "22") (pinfunction "22_22") (pintype "passive"))
      (node (ref "RP11") (pin "8") (pinfunction "8_8") (pintype "passive"))
    )
    (net (code "138") (name "/EXIO2_L15_N") (class "Default")
      (node (ref "PL_EXIO2") (pin "15") (pinfunction "15_15") (pintype "passive"))
      (node (ref "RP9") (pin "6") (pinfunction "6_6") (pintype "passive"))
    )
    (net (code "139") (name "/EXIO2_L15_P") (class "Default")
      (node (ref "PL_EXIO2") (pin "16") (pinfunction "16_16") (pintype "passive"))
      (node (ref "RP9") (pin "5") (pinfunction "5_5") (pintype "passive"))
    )
    (net (code "140") (name "/EXIO2_L16_N") (class "Default")
      (node (ref "PL_EXIO2") (pin "17") (pinfunction "17_17") (pintype "passive"))
      (node (ref "RP9") (pin "8") (pinfunction "8_8") (pintype "passive"))
    )
    (net (code "141") (name "/EXIO2_L16_P") (class "Default")
      (node (ref "PL_EXIO2") (pin "18") (pinfunction "18_18") (pintype "passive"))
      (node (ref "RP9") (pin "7") (pinfunction "7_7") (pintype "passive"))
    )
    (net (code "142") (name "/EXIO2_L17_N") (class "Default")
      (node (ref "PL_EXIO2") (pin "23") (pinfunction "23_23") (pintype "passive"))
      (node (ref "RP13") (pin "5") (pinfunction "5_5") (pintype "passive"))
    )
    (net (code "143") (name "/EXIO2_L17_P") (class "Default")
      (node (ref "PL_EXIO2") (pin "24") (pinfunction "24_24") (pintype "passive"))
      (node (ref "RP13") (pin "6") (pinfunction "6_6") (pintype "passive"))
    )
    (net (code "144") (name "/EXIO2_L22_N") (class "Default")
      (node (ref "PL_EXIO2") (pin "37") (pinfunction "37_37") (pintype "passive"))
      (node (ref "RP19") (pin "7") (pinfunction "7_7") (pintype "passive"))
    )
    (net (code "145") (name "/EXIO2_L22_P") (class "Default")
      (node (ref "PL_EXIO2") (pin "38") (pinfunction "38_38") (pintype "passive"))
      (node (ref "RP19") (pin "8") (pinfunction "8_8") (pintype "passive"))
    )
    (net (code "146") (name "/EXIO2_L23_N") (class "Default")
      (node (ref "PL_EXIO2") (pin "39") (pinfunction "39_39") (pintype "passive"))
      (node (ref "RP22") (pin "5") (pinfunction "5_5") (pintype "passive"))
    )
    (net (code "147") (name "/EXIO2_L23_P") (class "Default")
      (node (ref "PL_EXIO2") (pin "40") (pinfunction "40_40") (pintype "passive"))
      (node (ref "RP22") (pin "6") (pinfunction "6_6") (pintype "passive"))
    )
    (net (code "148") (name "/EX_PS_MIO7") (class "Default")
      (node (ref "PS_EXIO1") (pin "1") (pinfunction "1_1") (pintype "passive"))
      (node (ref "RP20") (pin "5") (pinfunction "5_5") (pintype "passive"))
    )
    (net (code "149") (name "/EX_PS_MIO8") (class "Default")
      (node (ref "PS_EXIO1") (pin "2") (pinfunction "2_2") (pintype "passive"))
      (node (ref "RP20") (pin "6") (pinfunction "6_6") (pintype "passive"))
    )
    (net (code "150") (name "/EX_PS_MIO9") (class "Default")
      (node (ref "PS_EXIO1") (pin "3") (pinfunction "3_3") (pintype "passive"))
      (node (ref "RP20") (pin "7") (pinfunction "7_7") (pintype "passive"))
    )
    (net (code "151") (name "/EX_PS_MIO10") (class "Default")
      (node (ref "PS_EXIO1") (pin "4") (pinfunction "4_4") (pintype "passive"))
      (node (ref "RP20") (pin "8") (pinfunction "8_8") (pintype "passive"))
    )
    (net (code "152") (name "/EX_PS_MIO11") (class "Default")
      (node (ref "PS_EXIO1") (pin "5") (pinfunction "5_5") (pintype "passive"))
      (node (ref "RP21") (pin "5") (pinfunction "5_5") (pintype "passive"))
    )
    (net (code "153") (name "/EX_PS_MIO12") (class "Default")
      (node (ref "PS_EXIO1") (pin "6") (pinfunction "6_6") (pintype "passive"))
      (node (ref "RP21") (pin "6") (pinfunction "6_6") (pintype "passive"))
    )
    (net (code "154") (name "/EX_PS_MIO14") (class "Default")
      (node (ref "PS_EXIO1") (pin "7") (pinfunction "7_7") (pintype "passive"))
      (node (ref "RP21") (pin "7") (pinfunction "7_7") (pintype "passive"))
    )
    (net (code "155") (name "/EX_PS_MIO15") (class "Default")
      (node (ref "PS_EXIO1") (pin "8") (pinfunction "8_8") (pintype "passive"))
      (node (ref "RP21") (pin "8") (pinfunction "8_8") (pintype "passive"))
    )
    (net (code "156") (name "/PS_MIO7") (class "Default")
      (node (ref "RP20") (pin "1") (pinfunction "1_1") (pintype "passive"))
    )
    (net (code "157") (name "/PS_MIO8") (class "Default")
      (node (ref "RP20") (pin "2") (pinfunction "2_2") (pintype "passive"))
    )
    (net (code "158") (name "/PS_MIO9") (class "Default")
      (node (ref "RP20") (pin "3") (pinfunction "3_3") (pintype "passive"))
    )
    (net (code "159") (name "/PS_MIO10") (class "Default")
      (node (ref "RP20") (pin "4") (pinfunction "4_4") (pintype "passive"))
    )
    (net (code "160") (name "/PS_MIO11") (class "Default")
      (node (ref "RP21") (pin "1") (pinfunction "1_1") (pintype "passive"))
    )
    (net (code "161") (name "/PS_MIO12") (class "Default")
      (node (ref "RP21") (pin "2") (pinfunction "2_2") (pintype "passive"))
    )
    (net (code "162") (name "/PS_MIO14") (class "Default")
      (node (ref "RP21") (pin "3") (pinfunction "3_3") (pintype "passive"))
    )
    (net (code "163") (name "/PS_MIO15") (class "Default")
      (node (ref "RP21") (pin "4") (pinfunction "4_4") (pintype "passive"))
    )
    (net (code "167") (name "D+3.3") (class "Default")
      (node (ref "C42") (pin "1") (pinfunction "1_1") (pintype "passive"))
      (node (ref "C43") (pin "1") (pinfunction "1_1") (pintype "passive"))
      (node (ref "PL_EXIO1") (pin "39") (pinfunction "39_39") (pintype "passive"))
      (node (ref "PL_EXIO1") (pin "40") (pinfunction "40_40") (pintype "passive"))
      (node (ref "PS_EXIO1") (pin "11") (pinfunction "11_11") (pintype "passive"))
      (node (ref "PS_EXIO1") (pin "12") (pinfunction "12_12") (pintype "passive"))
    )
    (net (code "168") (name "D+5") (class "Default")
      (node (ref "C44") (pin "1") (pinfunction "1_1") (pintype "passive"))
      (node (ref "C45") (pin "1") (pinfunction "1_1") (pintype "passive"))
      (node (ref "R157") (pin "2") (pinfunction "2_2") (pintype "passive"))
      (node (ref "R158") (pin "2") (pinfunction "2_2") (pintype "passive"))
    )
    (net (code "169") (name "DGND") (class "Default")
      (node (ref "C42") (pin "2") (pinfunction "2_2") (pintype "passive"))
      (node (ref "C43") (pin "2") (pinfunction "2_2") (pintype "passive"))
      (node (ref "C44") (pin "2") (pinfunction "2_2") (pintype "passive"))
      (node (ref "C45") (pin "2") (pinfunction "2_2") (pintype "passive"))
      (node (ref "PL_EXIO1") (pin "1") (pinfunction "1_1") (pintype "passive"))
      (node (ref "PL_EXIO1") (pin "37") (pinfunction "37_37") (pintype "passive"))
      (node (ref "PL_EXIO1") (pin "38") (pinfunction "38_38") (pintype "passive"))
      (node (ref "PL_EXIO2") (pin "1") (pinfunction "1_1") (pintype "passive"))
      (node (ref "PS_EXIO1") (pin "10") (pinfunction "10_10") (pintype "passive"))
      (node (ref "PS_EXIO1") (pin "9") (pinfunction "9_9") (pintype "passive"))
    )
    (net (code "170") (name "Net-(PL_EXIO1-Pad2)") (class "Default")
      (node (ref "PL_EXIO1") (pin "2") (pinfunction "2_2") (pintype "passive"))
      (node (ref "R157") (pin "1") (pinfunction "1_1") (pintype "passive"))
    )
    (net (code "171") (name "Net-(PL_EXIO2-Pad2)") (class "Default")
      (node (ref "PL_EXIO2") (pin "2") (pinfunction "2_2") (pintype "passive"))
      (node (ref "R158") (pin "1") (pinfunction "1_1") (pintype "passive"))
    )
    (net (code "172") (name "unconnected-(RP18-Pad3)") (class "Default")
      (node (ref "RP18") (pin "3") (pinfunction "3_3") (pintype "passive+no_connect"))
    )
    (net (code "173") (name "unconnected-(RP18-Pad4)") (class "Default")
      (node (ref "RP18") (pin "4") (pinfunction "4_4") (pintype "passive+no_connect"))
    )
    (net (code "174") (name "unconnected-(RP18-Pad7)") (class "Default")
      (node (ref "RP18") (pin "7") (pinfunction "7_7") (pintype "passive+no_connect"))
    )
    (net (code "175") (name "unconnected-(RP18-Pad8)") (class "Default")
      (node (ref "RP18") (pin "8") (pinfunction "8_8") (pintype "passive+no_connect"))
    )
    (net (code "176") (name "unconnected-(RP22-Pad3)") (class "Default")
      (node (ref "RP22") (pin "3") (pinfunction "3_3") (pintype "passive+no_connect"))
    )
    (net (code "177") (name "unconnected-(RP22-Pad4)") (class "Default")
      (node (ref "RP22") (pin "4") (pinfunction "4_4") (pintype "passive+no_connect"))
    )
    (net (code "178") (name "unconnected-(RP22-Pad7)") (class "Default")
      (node (ref "RP22") (pin "7") (pinfunction "7_7") (pintype "passive+no_connect"))
    )
    (net (code "179") (name "unconnected-(RP22-Pad8)") (class "Default")
      (node (ref "RP22") (pin "8") (pinfunction "8_8") (pintype "passive+no_connect"))
    )
  )
)
